# Nixie_Clock.net
KiCad netlist of a schematic drawn in Altium Designer
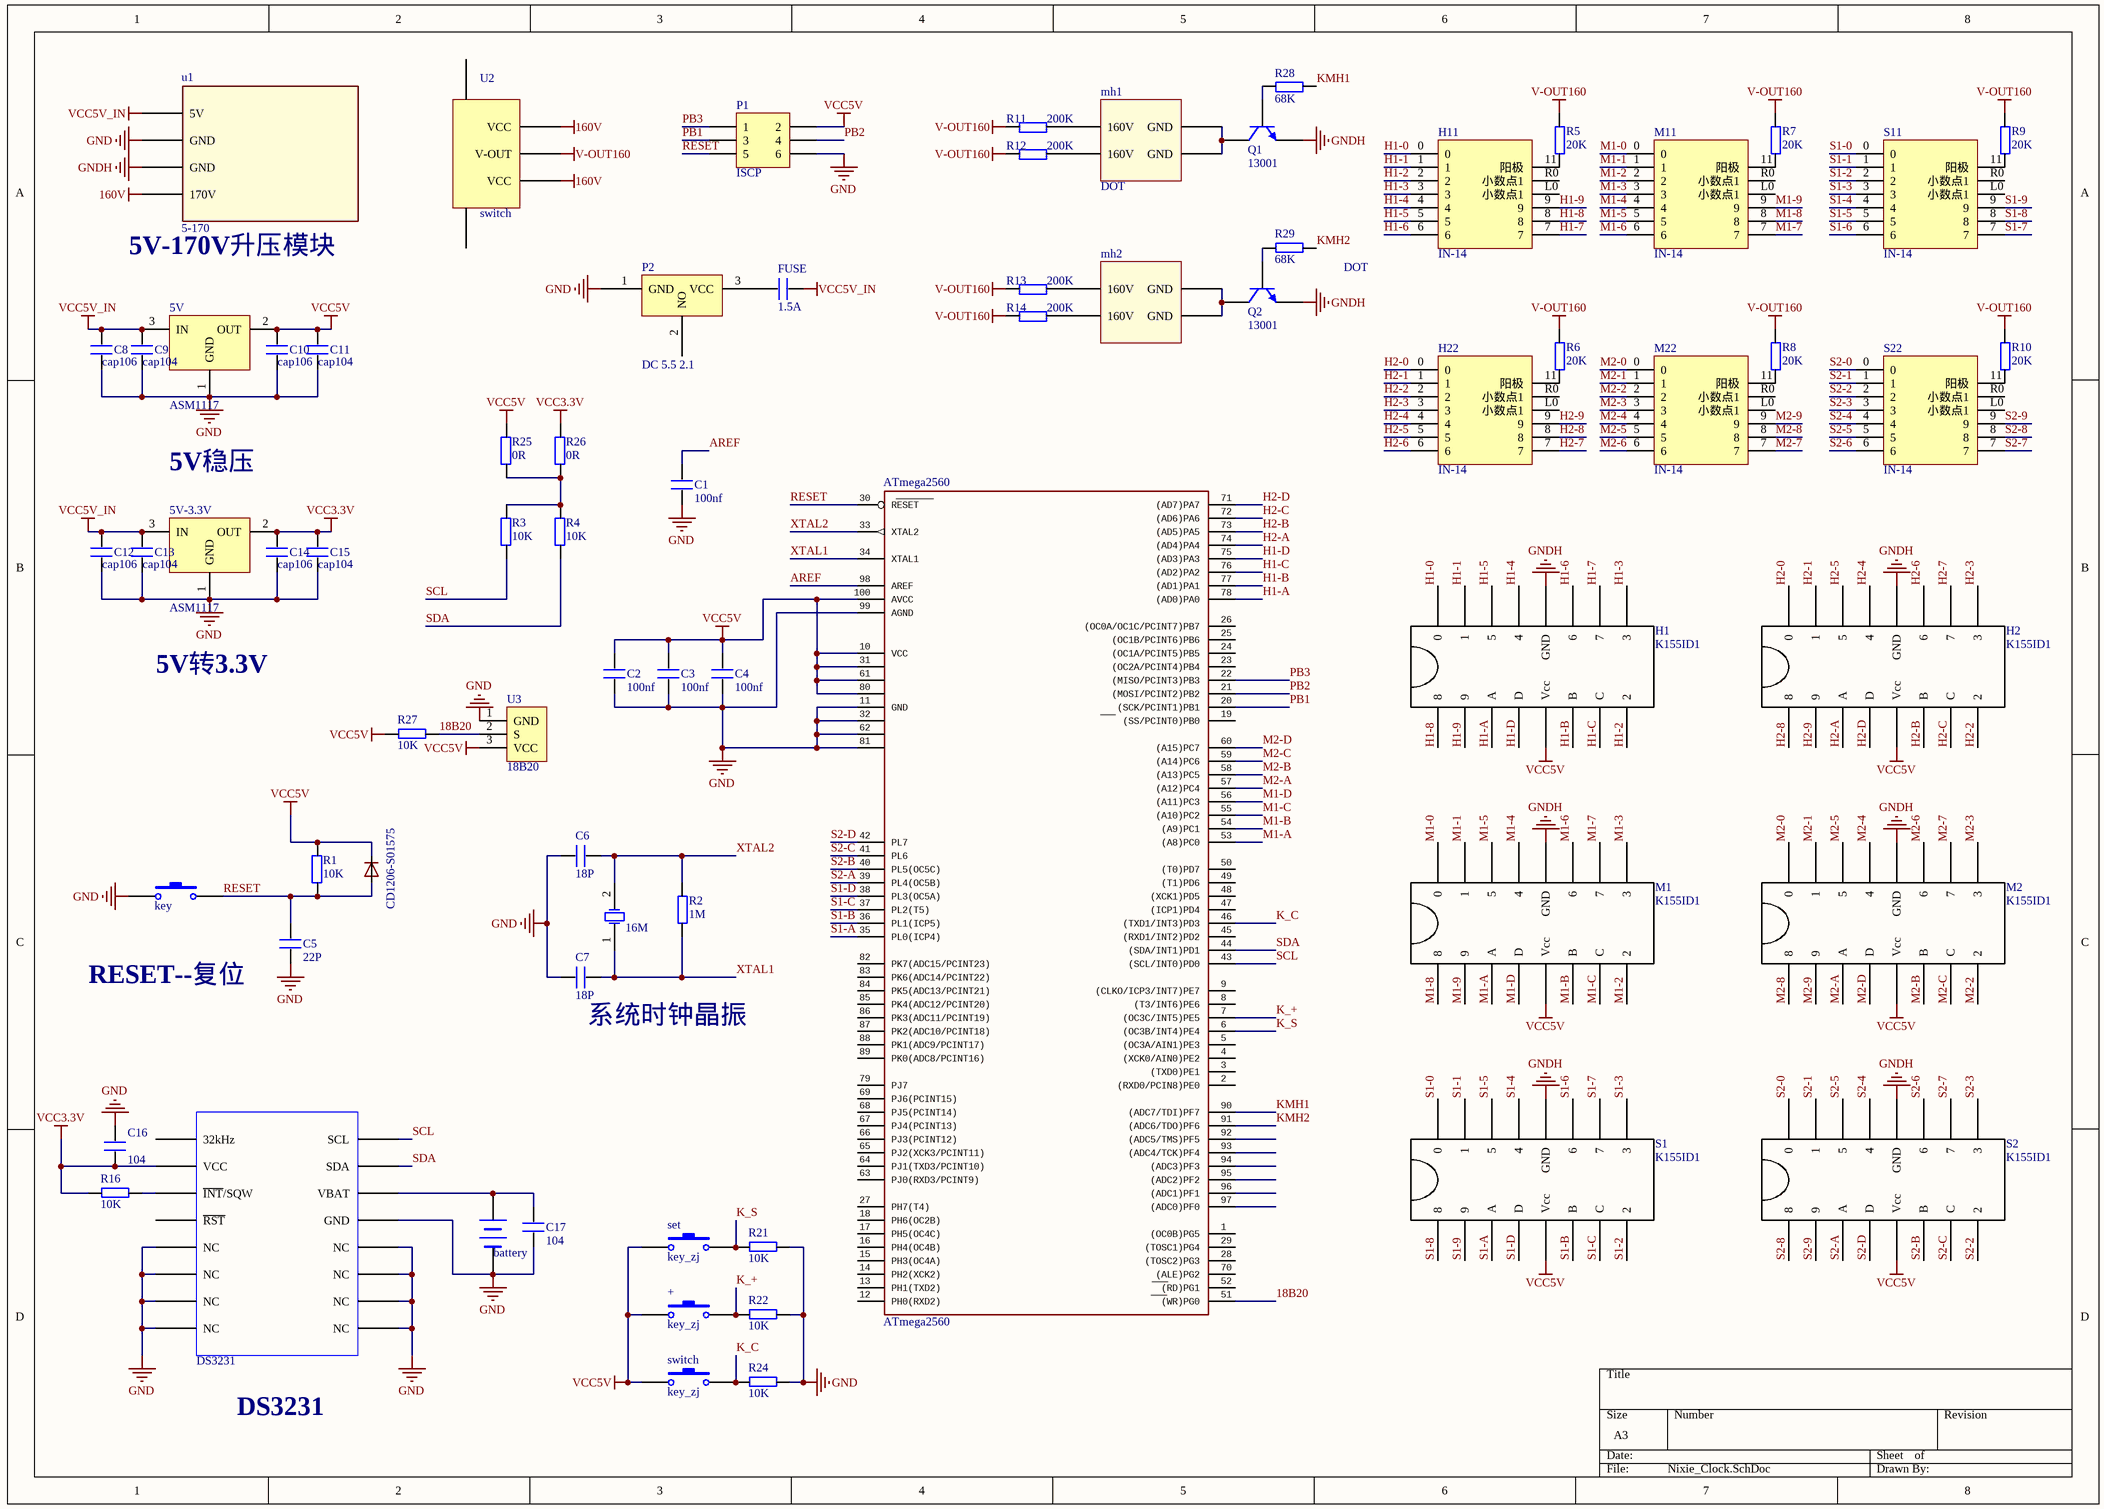
[diagram p0: Nixie_Clock.SchDoc]

(export (version "E")
  (design (tool "Eeschema 10.0.6"))
  (components
    (comp (ref "+") (value "key_zj") (footprint "key_zj") (libsource (lib "nixie") (part "key_zj")))
    (comp (ref "5V") (value "ASM1117") (footprint "AMS1117") (libsource (lib "nixie") (part "ASM1117")))
    (comp (ref "5V-3.3V") (value "ASM1117") (footprint "AMS1117") (libsource (lib "nixie") (part "ASM1117")))
    (comp (ref "ATmega2560")
      (value "ATmega2560")
      (footprint "ATmega2560")
      (libsource (lib "nixie") (part "ATmega2560"))
    )
    (comp (ref "bat") (value "battery") (footprint "battery") (libsource (lib "nixie") (part "battery")))
    (comp (ref "C1") (value "100nf") (footprint "0805_cap") (libsource (lib "nixie") (part "cap")))
    (comp (ref "C2") (value "100nf") (footprint "0805_cap") (libsource (lib "nixie") (part "cap")))
    (comp (ref "C3") (value "100nf") (footprint "0805_cap") (libsource (lib "nixie") (part "cap")))
    (comp (ref "C4") (value "100nf") (footprint "0805_cap") (libsource (lib "nixie") (part "cap")))
    (comp (ref "C5") (value "22P") (footprint "0805_cap") (libsource (lib "nixie") (part "cap")))
    (comp (ref "C6") (value "18P") (footprint "0805_cap") (libsource (lib "nixie") (part "cap")))
    (comp (ref "C7") (value "18P") (footprint "0805_cap") (libsource (lib "nixie") (part "cap")))
    (comp (ref "C8") (value "cap106") (footprint "1210_cap") (libsource (lib "nixie") (part "cap")))
    (comp (ref "C9") (value "cap104") (footprint "0805_cap") (libsource (lib "nixie") (part "cap")))
    (comp (ref "C10") (value "cap106") (footprint "1210_cap") (libsource (lib "nixie") (part "cap")))
    (comp (ref "C11") (value "cap104") (footprint "0805_cap") (libsource (lib "nixie") (part "cap")))
    (comp (ref "C12") (value "cap106") (footprint "1210_cap") (libsource (lib "nixie") (part "cap")))
    (comp (ref "C13") (value "cap104") (footprint "0805_cap") (libsource (lib "nixie") (part "cap")))
    (comp (ref "C14") (value "cap106") (footprint "1210_cap") (libsource (lib "nixie") (part "cap")))
    (comp (ref "C15") (value "cap104") (footprint "0805_cap") (libsource (lib "nixie") (part "cap")))
    (comp (ref "C16") (value "104") (footprint "0805_cap") (libsource (lib "nixie") (part "cap")))
    (comp (ref "C17") (value "104") (footprint "0805_cap") (libsource (lib "nixie") (part "cap")))
    (comp (ref "DIODE") (value "CD1206-S01575") (footprint "DIODE") (libsource (lib "nixie") (part "DIODE")))
    (comp (ref "ds3231") (value "DS3231") (footprint "DS3231") (libsource (lib "nixie") (part "DS3231")))
    (comp (ref "FUSE") (value "1.5A") (footprint "1210_cap") (libsource (lib "nixie") (part "cap")))
    (comp (ref "H1")
      (value "K155ID1")
      (footprint "Miscellaneous Devices:DIP-16")
      (libsource (lib "辉光钟第二版") (part "K155ID1"))
    )
    (comp (ref "H2")
      (value "K155ID1")
      (footprint "Miscellaneous Devices:DIP-16")
      (libsource (lib "辉光钟第二版") (part "K155ID1"))
    )
    (comp (ref "H11") (value "IN-14") (footprint "IN-14") (libsource (lib "nixie") (part "IN-14")))
    (comp (ref "H22") (value "IN-14") (footprint "IN-14") (libsource (lib "nixie") (part "IN-14")))
    (comp (ref "key") (value "key") (footprint "key") (libsource (lib "nixie") (part "key")))
    (comp (ref "M1")
      (value "K155ID1")
      (footprint "Miscellaneous Devices:DIP-16")
      (libsource (lib "辉光钟第二版") (part "K155ID1"))
    )
    (comp (ref "M2")
      (value "K155ID1")
      (footprint "Miscellaneous Devices:DIP-16")
      (libsource (lib "辉光钟第二版") (part "K155ID1"))
    )
    (comp (ref "M11") (value "IN-14") (footprint "IN-14") (libsource (lib "nixie") (part "IN-14")))
    (comp (ref "M22") (value "IN-14") (footprint "IN-14") (libsource (lib "nixie") (part "IN-14")))
    (comp (ref "mh1") (value "DOT") (footprint "dot") (libsource (lib "nixie") (part "DOT")))
    (comp (ref "mh2") (value "DOT") (footprint "dot") (libsource (lib "nixie") (part "DOT")))
    (comp (ref "P1")
      (value "ISCP")
      (footprint "HDR2X3")
      (description "Header, 3-Pin, Dual row")
      (fields (field (name "PUBLISHER") "Altium Limited"))
      (libsource (lib "Miscellaneous Connectors") (part "Header 3X2"))
    )
    (comp (ref "P2")
      (value "DC 5.5 2.1")
      (footprint "DC 5.5 2.1")
      (libsource (lib "nixie") (part "DC 5.5 2.1"))
    )
    (comp (ref "Q1") (value "13001") (footprint "13001") (libsource (lib "nixie") (part "13001")))
    (comp (ref "Q2") (value "13001") (footprint "13001") (libsource (lib "nixie") (part "13001")))
    (comp (ref "R1") (value "10K") (footprint "0805_res") (libsource (lib "nixie") (part "0805_res")))
    (comp (ref "R2") (value "1M") (footprint "0805_res") (libsource (lib "nixie") (part "0805_res")))
    (comp (ref "R3") (value "10K") (footprint "0805_res") (libsource (lib "nixie") (part "0805_res")))
    (comp (ref "R4") (value "10K") (footprint "0805_res") (libsource (lib "nixie") (part "0805_res")))
    (comp (ref "R5") (value "20K") (footprint "0805_res") (libsource (lib "nixie") (part "0805_res")))
    (comp (ref "R6") (value "20K") (footprint "0805_res") (libsource (lib "nixie") (part "0805_res")))
    (comp (ref "R7") (value "20K") (footprint "0805_res") (libsource (lib "nixie") (part "0805_res")))
    (comp (ref "R8") (value "20K") (footprint "0805_res") (libsource (lib "nixie") (part "0805_res")))
    (comp (ref "R9") (value "20K") (footprint "0805_res") (libsource (lib "nixie") (part "0805_res")))
    (comp (ref "R10") (value "20K") (footprint "0805_res") (libsource (lib "nixie") (part "0805_res")))
    (comp (ref "R11") (value "200K") (footprint "0805_res") (libsource (lib "nixie") (part "0805_res")))
    (comp (ref "R12") (value "200K") (footprint "0805_res") (libsource (lib "nixie") (part "0805_res")))
    (comp (ref "R13") (value "200K") (footprint "0805_res") (libsource (lib "nixie") (part "0805_res")))
    (comp (ref "R14") (value "200K") (footprint "0805_res") (libsource (lib "nixie") (part "0805_res")))
    (comp (ref "R16") (value "10K") (footprint "0805_res") (libsource (lib "nixie") (part "0805_res")))
    (comp (ref "R21") (value "10K") (footprint "0805_res") (libsource (lib "nixie") (part "0805_res")))
    (comp (ref "R22") (value "10K") (footprint "0805_res") (libsource (lib "nixie") (part "0805_res")))
    (comp (ref "R24") (value "10K") (footprint "0805_res") (libsource (lib "nixie") (part "0805_res")))
    (comp (ref "R25") (value "0R") (footprint "0805_res") (libsource (lib "nixie") (part "0805_res")))
    (comp (ref "R26") (value "0R") (footprint "0805_res") (libsource (lib "nixie") (part "0805_res")))
    (comp (ref "R27") (value "10K") (footprint "0805_res") (libsource (lib "nixie") (part "0805_res")))
    (comp (ref "R28") (value "68K") (footprint "0805_res") (libsource (lib "nixie") (part "0805_res")))
    (comp (ref "R29") (value "68K") (footprint "0805_res") (libsource (lib "nixie") (part "0805_res")))
    (comp (ref "S1")
      (value "K155ID1")
      (footprint "Miscellaneous Devices:DIP-16")
      (libsource (lib "辉光钟第二版") (part "K155ID1"))
    )
    (comp (ref "S2")
      (value "K155ID1")
      (footprint "Miscellaneous Devices:DIP-16")
      (libsource (lib "辉光钟第二版") (part "K155ID1"))
    )
    (comp (ref "S11") (value "IN-14") (footprint "IN-14") (libsource (lib "nixie") (part "IN-14")))
    (comp (ref "S22") (value "IN-14") (footprint "IN-14") (libsource (lib "nixie") (part "IN-14")))
    (comp (ref "set") (value "key_zj") (footprint "key_zj") (libsource (lib "nixie") (part "key_zj")))
    (comp (ref "switch") (value "key_zj") (footprint "key_zj") (libsource (lib "nixie") (part "key_zj")))
    (comp (ref "u1") (value "5-170") (footprint "5-170V") (libsource (lib "nixie") (part "5-170")))
    (comp (ref "U2") (value "switch") (footprint "switch") (libsource (lib "nixie") (part "switch")))
    (comp (ref "U3") (value "18B20") (footprint "18B20") (libsource (lib "nixie") (part "18B20")))
    (comp (ref "Y1") (value "16M") (footprint "XTAL") (libsource (lib "nixie") (part "xtal")))
  )
  (nets
    (net (code "1") (name "/18B20") (class "Default")
      (node (ref "ATmega2560") (pin "51") (pinfunction "(WR)PG0_51") (pintype "passive"))
      (node (ref "R27") (pin "1") (pintype "passive"))
      (node (ref "U3") (pin "2") (pinfunction "S_2") (pintype "passive"))
    )
    (net (code "2") (name "/AREF") (class "Default")
      (node (ref "ATmega2560") (pin "98") (pinfunction "AREF_98") (pintype "passive"))
      (node (ref "C1") (pin "2") (pintype "passive"))
    )
    (net (code "3") (name "/H1-0") (class "Default")
      (node (ref "H1") (pin "16") (pinfunction "0_16") (pintype "passive"))
      (node (ref "H11") (pin "0") (pinfunction "0_0") (pintype "passive"))
    )
    (net (code "4") (name "/H1-1") (class "Default")
      (node (ref "H1") (pin "15") (pinfunction "1_15") (pintype "passive"))
      (node (ref "H11") (pin "1") (pinfunction "1_1") (pintype "passive"))
    )
    (net (code "5") (name "/H1-2") (class "Default")
      (node (ref "H1") (pin "8") (pinfunction "2_8") (pintype "passive"))
      (node (ref "H11") (pin "2") (pinfunction "2_2") (pintype "passive"))
    )
    (net (code "6") (name "/H1-3") (class "Default")
      (node (ref "H1") (pin "9") (pinfunction "3_9") (pintype "passive"))
      (node (ref "H11") (pin "3") (pinfunction "3_3") (pintype "passive"))
    )
    (net (code "7") (name "/H1-4") (class "Default")
      (node (ref "H1") (pin "13") (pinfunction "4_13") (pintype "passive"))
      (node (ref "H11") (pin "4") (pinfunction "4_4") (pintype "passive"))
    )
    (net (code "8") (name "/H1-5") (class "Default")
      (node (ref "H1") (pin "14") (pinfunction "5_14") (pintype "passive"))
      (node (ref "H11") (pin "5") (pinfunction "5_5") (pintype "passive"))
    )
    (net (code "9") (name "/H1-6") (class "Default")
      (node (ref "H1") (pin "11") (pinfunction "6_11") (pintype "passive"))
      (node (ref "H11") (pin "6") (pinfunction "6_6") (pintype "passive"))
    )
    (net (code "10") (name "/H1-7") (class "Default")
      (node (ref "H1") (pin "10") (pinfunction "7_10") (pintype "passive"))
      (node (ref "H11") (pin "7") (pinfunction "7_7") (pintype "passive"))
    )
    (net (code "11") (name "/H1-8") (class "Default")
      (node (ref "H1") (pin "1") (pinfunction "8_1") (pintype "passive"))
      (node (ref "H11") (pin "8") (pinfunction "8_8") (pintype "passive"))
    )
    (net (code "12") (name "/H1-9") (class "Default")
      (node (ref "H1") (pin "2") (pinfunction "9_2") (pintype "passive"))
      (node (ref "H11") (pin "9") (pinfunction "9_9") (pintype "passive"))
    )
    (net (code "13") (name "/H1-A") (class "Default")
      (node (ref "ATmega2560") (pin "78") (pinfunction "(AD0)PA0_78") (pintype "passive"))
      (node (ref "H1") (pin "3") (pinfunction "A_3") (pintype "passive"))
    )
    (net (code "14") (name "/H1-B") (class "Default")
      (node (ref "ATmega2560") (pin "77") (pinfunction "(AD1)PA1_77") (pintype "passive"))
      (node (ref "H1") (pin "6") (pinfunction "B_6") (pintype "passive"))
    )
    (net (code "15") (name "/H1-C") (class "Default")
      (node (ref "ATmega2560") (pin "76") (pinfunction "(AD2)PA2_76") (pintype "passive"))
      (node (ref "H1") (pin "7") (pinfunction "C_7") (pintype "passive"))
    )
    (net (code "16") (name "/H1-D") (class "Default")
      (node (ref "ATmega2560") (pin "75") (pinfunction "(AD3)PA3_75") (pintype "passive"))
      (node (ref "H1") (pin "4") (pinfunction "D_4") (pintype "passive"))
    )
    (net (code "17") (name "/H2-0") (class "Default")
      (node (ref "H2") (pin "16") (pinfunction "0_16") (pintype "passive"))
      (node (ref "H22") (pin "0") (pinfunction "0_0") (pintype "passive"))
    )
    (net (code "18") (name "/H2-1") (class "Default")
      (node (ref "H2") (pin "15") (pinfunction "1_15") (pintype "passive"))
      (node (ref "H22") (pin "1") (pinfunction "1_1") (pintype "passive"))
    )
    (net (code "19") (name "/H2-2") (class "Default")
      (node (ref "H2") (pin "8") (pinfunction "2_8") (pintype "passive"))
      (node (ref "H22") (pin "2") (pinfunction "2_2") (pintype "passive"))
    )
    (net (code "20") (name "/H2-3") (class "Default")
      (node (ref "H2") (pin "9") (pinfunction "3_9") (pintype "passive"))
      (node (ref "H22") (pin "3") (pinfunction "3_3") (pintype "passive"))
    )
    (net (code "21") (name "/H2-4") (class "Default")
      (node (ref "H2") (pin "13") (pinfunction "4_13") (pintype "passive"))
      (node (ref "H22") (pin "4") (pinfunction "4_4") (pintype "passive"))
    )
    (net (code "22") (name "/H2-5") (class "Default")
      (node (ref "H2") (pin "14") (pinfunction "5_14") (pintype "passive"))
      (node (ref "H22") (pin "5") (pinfunction "5_5") (pintype "passive"))
    )
    (net (code "23") (name "/H2-6") (class "Default")
      (node (ref "H2") (pin "11") (pinfunction "6_11") (pintype "passive"))
      (node (ref "H22") (pin "6") (pinfunction "6_6") (pintype "passive"))
    )
    (net (code "24") (name "/H2-7") (class "Default")
      (node (ref "H2") (pin "10") (pinfunction "7_10") (pintype "passive"))
      (node (ref "H22") (pin "7") (pinfunction "7_7") (pintype "passive"))
    )
    (net (code "25") (name "/H2-8") (class "Default")
      (node (ref "H2") (pin "1") (pinfunction "8_1") (pintype "passive"))
      (node (ref "H22") (pin "8") (pinfunction "8_8") (pintype "passive"))
    )
    (net (code "26") (name "/H2-9") (class "Default")
      (node (ref "H2") (pin "2") (pinfunction "9_2") (pintype "passive"))
      (node (ref "H22") (pin "9") (pinfunction "9_9") (pintype "passive"))
    )
    (net (code "27") (name "/H2-A") (class "Default")
      (node (ref "ATmega2560") (pin "74") (pinfunction "(AD4)PA4_74") (pintype "passive"))
      (node (ref "H2") (pin "3") (pinfunction "A_3") (pintype "passive"))
    )
    (net (code "28") (name "/H2-B") (class "Default")
      (node (ref "ATmega2560") (pin "73") (pinfunction "(AD5)PA5_73") (pintype "passive"))
      (node (ref "H2") (pin "6") (pinfunction "B_6") (pintype "passive"))
    )
    (net (code "29") (name "/H2-C") (class "Default")
      (node (ref "ATmega2560") (pin "72") (pinfunction "(AD6)PA6_72") (pintype "passive"))
      (node (ref "H2") (pin "7") (pinfunction "C_7") (pintype "passive"))
    )
    (net (code "30") (name "/H2-D") (class "Default")
      (node (ref "ATmega2560") (pin "71") (pinfunction "(AD7)PA7_71") (pintype "passive"))
      (node (ref "H2") (pin "4") (pinfunction "D_4") (pintype "passive"))
    )
    (net (code "31") (name "/KMH1") (class "Default")
      (node (ref "ATmega2560") (pin "90") (pinfunction "(ADC7/TDI)PF7_90") (pintype "passive"))
      (node (ref "R28") (pin "2") (pintype "passive"))
    )
    (net (code "32") (name "/KMH2") (class "Default")
      (node (ref "ATmega2560") (pin "91") (pinfunction "(ADC6/TDO)PF6_91") (pintype "passive"))
      (node (ref "R29") (pin "1") (pintype "passive"))
    )
    (net (code "33") (name "/K_+") (class "Default")
      (node (ref "+") (pin "2") (pinfunction "2_2") (pintype "passive"))
      (node (ref "ATmega2560") (pin "7") (pinfunction "(OC3C/INT5)PE5_7") (pintype "passive"))
      (node (ref "R22") (pin "2") (pintype "passive"))
    )
    (net (code "34") (name "/K_C") (class "Default")
      (node (ref "ATmega2560") (pin "46") (pinfunction "(TXD1/INT3)PD3_46") (pintype "passive"))
      (node (ref "R24") (pin "2") (pintype "passive"))
      (node (ref "switch") (pin "2") (pinfunction "2_2") (pintype "passive"))
    )
    (net (code "35") (name "/K_S") (class "Default")
      (node (ref "ATmega2560") (pin "6") (pinfunction "(OC3B/INT4)PE4_6") (pintype "passive"))
      (node (ref "R21") (pin "2") (pintype "passive"))
      (node (ref "set") (pin "2") (pinfunction "2_2") (pintype "passive"))
    )
    (net (code "36") (name "/M1-0") (class "Default")
      (node (ref "M1") (pin "16") (pinfunction "0_16") (pintype "passive"))
      (node (ref "M11") (pin "0") (pinfunction "0_0") (pintype "passive"))
    )
    (net (code "37") (name "/M1-1") (class "Default")
      (node (ref "M1") (pin "15") (pinfunction "1_15") (pintype "passive"))
      (node (ref "M11") (pin "1") (pinfunction "1_1") (pintype "passive"))
    )
    (net (code "38") (name "/M1-2") (class "Default")
      (node (ref "M1") (pin "8") (pinfunction "2_8") (pintype "passive"))
      (node (ref "M11") (pin "2") (pinfunction "2_2") (pintype "passive"))
    )
    (net (code "39") (name "/M1-3") (class "Default")
      (node (ref "M1") (pin "9") (pinfunction "3_9") (pintype "passive"))
      (node (ref "M11") (pin "3") (pinfunction "3_3") (pintype "passive"))
    )
    (net (code "40") (name "/M1-4") (class "Default")
      (node (ref "M1") (pin "13") (pinfunction "4_13") (pintype "passive"))
      (node (ref "M11") (pin "4") (pinfunction "4_4") (pintype "passive"))
    )
    (net (code "41") (name "/M1-5") (class "Default")
      (node (ref "M1") (pin "14") (pinfunction "5_14") (pintype "passive"))
      (node (ref "M11") (pin "5") (pinfunction "5_5") (pintype "passive"))
    )
    (net (code "42") (name "/M1-6") (class "Default")
      (node (ref "M1") (pin "11") (pinfunction "6_11") (pintype "passive"))
      (node (ref "M11") (pin "6") (pinfunction "6_6") (pintype "passive"))
    )
    (net (code "43") (name "/M1-7") (class "Default")
      (node (ref "M1") (pin "10") (pinfunction "7_10") (pintype "passive"))
      (node (ref "M11") (pin "7") (pinfunction "7_7") (pintype "passive"))
    )
    (net (code "44") (name "/M1-8") (class "Default")
      (node (ref "M1") (pin "1") (pinfunction "8_1") (pintype "passive"))
      (node (ref "M11") (pin "8") (pinfunction "8_8") (pintype "passive"))
    )
    (net (code "45") (name "/M1-9") (class "Default")
      (node (ref "M1") (pin "2") (pinfunction "9_2") (pintype "passive"))
      (node (ref "M11") (pin "9") (pinfunction "9_9") (pintype "passive"))
    )
    (net (code "46") (name "/M1-A") (class "Default")
      (node (ref "ATmega2560") (pin "53") (pinfunction "(A8)PC0_53") (pintype "passive"))
      (node (ref "M1") (pin "3") (pinfunction "A_3") (pintype "passive"))
    )
    (net (code "47") (name "/M1-B") (class "Default")
      (node (ref "ATmega2560") (pin "54") (pinfunction "(A9)PC1_54") (pintype "passive"))
      (node (ref "M1") (pin "6") (pinfunction "B_6") (pintype "passive"))
    )
    (net (code "48") (name "/M1-C") (class "Default")
      (node (ref "ATmega2560") (pin "55") (pinfunction "(A10)PC2_55") (pintype "passive"))
      (node (ref "M1") (pin "7") (pinfunction "C_7") (pintype "passive"))
    )
    (net (code "49") (name "/M1-D") (class "Default")
      (node (ref "ATmega2560") (pin "56") (pinfunction "(A11)PC3_56") (pintype "passive"))
      (node (ref "M1") (pin "4") (pinfunction "D_4") (pintype "passive"))
    )
    (net (code "50") (name "/M2-0") (class "Default")
      (node (ref "M2") (pin "16") (pinfunction "0_16") (pintype "passive"))
      (node (ref "M22") (pin "0") (pinfunction "0_0") (pintype "passive"))
    )
    (net (code "51") (name "/M2-1") (class "Default")
      (node (ref "M2") (pin "15") (pinfunction "1_15") (pintype "passive"))
      (node (ref "M22") (pin "1") (pinfunction "1_1") (pintype "passive"))
    )
    (net (code "52") (name "/M2-2") (class "Default")
      (node (ref "M2") (pin "8") (pinfunction "2_8") (pintype "passive"))
      (node (ref "M22") (pin "2") (pinfunction "2_2") (pintype "passive"))
    )
    (net (code "53") (name "/M2-3") (class "Default")
      (node (ref "M2") (pin "9") (pinfunction "3_9") (pintype "passive"))
      (node (ref "M22") (pin "3") (pinfunction "3_3") (pintype "passive"))
    )
    (net (code "54") (name "/M2-4") (class "Default")
      (node (ref "M2") (pin "13") (pinfunction "4_13") (pintype "passive"))
      (node (ref "M22") (pin "4") (pinfunction "4_4") (pintype "passive"))
    )
    (net (code "55") (name "/M2-5") (class "Default")
      (node (ref "M2") (pin "14") (pinfunction "5_14") (pintype "passive"))
      (node (ref "M22") (pin "5") (pinfunction "5_5") (pintype "passive"))
    )
    (net (code "56") (name "/M2-6") (class "Default")
      (node (ref "M2") (pin "11") (pinfunction "6_11") (pintype "passive"))
      (node (ref "M22") (pin "6") (pinfunction "6_6") (pintype "passive"))
    )
    (net (code "57") (name "/M2-7") (class "Default")
      (node (ref "M2") (pin "10") (pinfunction "7_10") (pintype "passive"))
      (node (ref "M22") (pin "7") (pinfunction "7_7") (pintype "passive"))
    )
    (net (code "58") (name "/M2-8") (class "Default")
      (node (ref "M2") (pin "1") (pinfunction "8_1") (pintype "passive"))
      (node (ref "M22") (pin "8") (pinfunction "8_8") (pintype "passive"))
    )
    (net (code "59") (name "/M2-9") (class "Default")
      (node (ref "M2") (pin "2") (pinfunction "9_2") (pintype "passive"))
      (node (ref "M22") (pin "9") (pinfunction "9_9") (pintype "passive"))
    )
    (net (code "60") (name "/M2-A") (class "Default")
      (node (ref "ATmega2560") (pin "57") (pinfunction "(A12)PC4_57") (pintype "passive"))
      (node (ref "M2") (pin "3") (pinfunction "A_3") (pintype "passive"))
    )
    (net (code "61") (name "/M2-B") (class "Default")
      (node (ref "ATmega2560") (pin "58") (pinfunction "(A13)PC5_58") (pintype "passive"))
      (node (ref "M2") (pin "6") (pinfunction "B_6") (pintype "passive"))
    )
    (net (code "62") (name "/M2-C") (class "Default")
      (node (ref "ATmega2560") (pin "59") (pinfunction "(A14)PC6_59") (pintype "passive"))
      (node (ref "M2") (pin "7") (pinfunction "C_7") (pintype "passive"))
    )
    (net (code "63") (name "/M2-D") (class "Default")
      (node (ref "ATmega2560") (pin "60") (pinfunction "(A15)PC7_60") (pintype "passive"))
      (node (ref "M2") (pin "4") (pinfunction "D_4") (pintype "passive"))
    )
    (net (code "64") (name "/PB1") (class "Default")
      (node (ref "ATmega2560") (pin "20") (pinfunction "(SCK/PCINT1)PB1_20") (pintype "passive"))
      (node (ref "P1") (pin "3") (pinfunction "3_3") (pintype "passive"))
    )
    (net (code "65") (name "/PB2") (class "Default")
      (node (ref "ATmega2560") (pin "21") (pinfunction "(MOSI/PCINT2)PB2_21") (pintype "passive"))
      (node (ref "P1") (pin "4") (pinfunction "4_4") (pintype "passive"))
    )
    (net (code "66") (name "/PB3") (class "Default")
      (node (ref "ATmega2560") (pin "22") (pinfunction "(MISO/PCINT3)PB3_22") (pintype "passive"))
      (node (ref "P1") (pin "1") (pinfunction "1_1") (pintype "passive"))
    )
    (net (code "67") (name "/RESET") (class "Default")
      (node (ref "ATmega2560") (pin "30") (pinfunction "RESET_30") (pintype "passive"))
      (node (ref "C5") (pin "2") (pintype "passive"))
      (node (ref "DIODE") (pin "A") (pinfunction "A_A") (pintype "passive"))
      (node (ref "P1") (pin "5") (pinfunction "5_5") (pintype "passive"))
      (node (ref "R1") (pin "2") (pintype "passive"))
      (node (ref "key") (pin "2") (pinfunction "2_2") (pintype "passive"))
    )
    (net (code "68") (name "/S1-0") (class "Default")
      (node (ref "S1") (pin "16") (pinfunction "0_16") (pintype "passive"))
      (node (ref "S11") (pin "0") (pinfunction "0_0") (pintype "passive"))
    )
    (net (code "69") (name "/S1-1") (class "Default")
      (node (ref "S1") (pin "15") (pinfunction "1_15") (pintype "passive"))
      (node (ref "S11") (pin "1") (pinfunction "1_1") (pintype "passive"))
    )
    (net (code "70") (name "/S1-2") (class "Default")
      (node (ref "S1") (pin "8") (pinfunction "2_8") (pintype "passive"))
      (node (ref "S11") (pin "2") (pinfunction "2_2") (pintype "passive"))
    )
    (net (code "71") (name "/S1-3") (class "Default")
      (node (ref "S1") (pin "9") (pinfunction "3_9") (pintype "passive"))
      (node (ref "S11") (pin "3") (pinfunction "3_3") (pintype "passive"))
    )
    (net (code "72") (name "/S1-4") (class "Default")
      (node (ref "S1") (pin "13") (pinfunction "4_13") (pintype "passive"))
      (node (ref "S11") (pin "4") (pinfunction "4_4") (pintype "passive"))
    )
    (net (code "73") (name "/S1-5") (class "Default")
      (node (ref "S1") (pin "14") (pinfunction "5_14") (pintype "passive"))
      (node (ref "S11") (pin "5") (pinfunction "5_5") (pintype "passive"))
    )
    (net (code "74") (name "/S1-6") (class "Default")
      (node (ref "S1") (pin "11") (pinfunction "6_11") (pintype "passive"))
      (node (ref "S11") (pin "6") (pinfunction "6_6") (pintype "passive"))
    )
    (net (code "75") (name "/S1-7") (class "Default")
      (node (ref "S1") (pin "10") (pinfunction "7_10") (pintype "passive"))
      (node (ref "S11") (pin "7") (pinfunction "7_7") (pintype "passive"))
    )
    (net (code "76") (name "/S1-8") (class "Default")
      (node (ref "S1") (pin "1") (pinfunction "8_1") (pintype "passive"))
      (node (ref "S11") (pin "8") (pinfunction "8_8") (pintype "passive"))
    )
    (net (code "77") (name "/S1-9") (class "Default")
      (node (ref "S1") (pin "2") (pinfunction "9_2") (pintype "passive"))
      (node (ref "S11") (pin "9") (pinfunction "9_9") (pintype "passive"))
    )
    (net (code "78") (name "/S1-A") (class "Default")
      (node (ref "ATmega2560") (pin "35") (pinfunction "PL0(ICP4)_35") (pintype "passive"))
      (node (ref "S1") (pin "3") (pinfunction "A_3") (pintype "passive"))
    )
    (net (code "79") (name "/S1-B") (class "Default")
      (node (ref "ATmega2560") (pin "36") (pinfunction "PL1(ICP5)_36") (pintype "passive"))
      (node (ref "S1") (pin "6") (pinfunction "B_6") (pintype "passive"))
    )
    (net (code "80") (name "/S1-C") (class "Default")
      (node (ref "ATmega2560") (pin "37") (pinfunction "PL2(T5)_37") (pintype "passive"))
      (node (ref "S1") (pin "7") (pinfunction "C_7") (pintype "passive"))
    )
    (net (code "81") (name "/S1-D") (class "Default")
      (node (ref "ATmega2560") (pin "38") (pinfunction "PL3(OC5A)_38") (pintype "passive"))
      (node (ref "S1") (pin "4") (pinfunction "D_4") (pintype "passive"))
    )
    (net (code "82") (name "/S2-0") (class "Default")
      (node (ref "S2") (pin "16") (pinfunction "0_16") (pintype "passive"))
      (node (ref "S22") (pin "0") (pinfunction "0_0") (pintype "passive"))
    )
    (net (code "83") (name "/S2-1") (class "Default")
      (node (ref "S2") (pin "15") (pinfunction "1_15") (pintype "passive"))
      (node (ref "S22") (pin "1") (pinfunction "1_1") (pintype "passive"))
    )
    (net (code "84") (name "/S2-2") (class "Default")
      (node (ref "S2") (pin "8") (pinfunction "2_8") (pintype "passive"))
      (node (ref "S22") (pin "2") (pinfunction "2_2") (pintype "passive"))
    )
    (net (code "85") (name "/S2-3") (class "Default")
      (node (ref "S2") (pin "9") (pinfunction "3_9") (pintype "passive"))
      (node (ref "S22") (pin "3") (pinfunction "3_3") (pintype "passive"))
    )
    (net (code "86") (name "/S2-4") (class "Default")
      (node (ref "S2") (pin "13") (pinfunction "4_13") (pintype "passive"))
      (node (ref "S22") (pin "4") (pinfunction "4_4") (pintype "passive"))
    )
    (net (code "87") (name "/S2-5") (class "Default")
      (node (ref "S2") (pin "14") (pinfunction "5_14") (pintype "passive"))
      (node (ref "S22") (pin "5") (pinfunction "5_5") (pintype "passive"))
    )
    (net (code "88") (name "/S2-6") (class "Default")
      (node (ref "S2") (pin "11") (pinfunction "6_11") (pintype "passive"))
      (node (ref "S22") (pin "6") (pinfunction "6_6") (pintype "passive"))
    )
    (net (code "89") (name "/S2-7") (class "Default")
      (node (ref "S2") (pin "10") (pinfunction "7_10") (pintype "passive"))
      (node (ref "S22") (pin "7") (pinfunction "7_7") (pintype "passive"))
    )
    (net (code "90") (name "/S2-8") (class "Default")
      (node (ref "S2") (pin "1") (pinfunction "8_1") (pintype "passive"))
      (node (ref "S22") (pin "8") (pinfunction "8_8") (pintype "passive"))
    )
    (net (code "91") (name "/S2-9") (class "Default")
      (node (ref "S2") (pin "2") (pinfunction "9_2") (pintype "passive"))
      (node (ref "S22") (pin "9") (pinfunction "9_9") (pintype "passive"))
    )
    (net (code "92") (name "/S2-A") (class "Default")
      (node (ref "ATmega2560") (pin "39") (pinfunction "PL4(OC5B)_39") (pintype "passive"))
      (node (ref "S2") (pin "3") (pinfunction "A_3") (pintype "passive"))
    )
    (net (code "93") (name "/S2-B") (class "Default")
      (node (ref "ATmega2560") (pin "40") (pinfunction "PL5(OC5C)_40") (pintype "passive"))
      (node (ref "S2") (pin "6") (pinfunction "B_6") (pintype "passive"))
    )
    (net (code "94") (name "/S2-C") (class "Default")
      (node (ref "ATmega2560") (pin "41") (pinfunction "PL6_41") (pintype "passive"))
      (node (ref "S2") (pin "7") (pinfunction "C_7") (pintype "passive"))
    )
    (net (code "95") (name "/S2-D") (class "Default")
      (node (ref "ATmega2560") (pin "42") (pinfunction "PL7_42") (pintype "passive"))
      (node (ref "S2") (pin "4") (pinfunction "D_4") (pintype "passive"))
    )
    (net (code "96") (name "/SCL") (class "Default")
      (node (ref "ATmega2560") (pin "43") (pinfunction "(SCL/INT0)PD0_43") (pintype "passive"))
      (node (ref "R3") (pin "2") (pintype "passive"))
      (node (ref "ds3231") (pin "16") (pinfunction "SCL_16") (pintype "passive"))
    )
    (net (code "97") (name "/SDA") (class "Default")
      (node (ref "ATmega2560") (pin "44") (pinfunction "(SDA/INT1)PD1_44") (pintype "passive"))
      (node (ref "R4") (pin "2") (pintype "passive"))
      (node (ref "ds3231") (pin "15") (pinfunction "SDA_15") (pintype "passive"))
    )
    (net (code "98") (name "/XTAL1") (class "Default")
      (node (ref "ATmega2560") (pin "34") (pinfunction "XTAL1_34") (pintype "passive"))
      (node (ref "C7") (pin "1") (pintype "passive"))
      (node (ref "R2") (pin "1") (pintype "passive"))
      (node (ref "Y1") (pin "1") (pinfunction "OSC1_1") (pintype "passive"))
    )
    (net (code "99") (name "/XTAL2") (class "Default")
      (node (ref "ATmega2560") (pin "33") (pinfunction "XTAL2_33") (pintype "output"))
      (node (ref "C6") (pin "1") (pintype "passive"))
      (node (ref "R2") (pin "2") (pintype "passive"))
      (node (ref "Y1") (pin "2") (pinfunction "OSC2_2") (pintype "passive"))
    )
    (net (code "100") (name "160V") (class "Default")
      (node (ref "U2") (pin "1") (pinfunction "VCC_1") (pintype "passive"))
      (node (ref "U2") (pin "3") (pinfunction "VCC_3") (pintype "passive"))
      (node (ref "u1") (pin "4") (pinfunction "170V_4") (pintype "passive"))
    )
    (net (code "101") (name "GND") (class "Default")
      (node (ref "5V") (pin "1") (pinfunction "GND_1") (pintype "passive"))
      (node (ref "5V-3.3V") (pin "1") (pinfunction "GND_1") (pintype "passive"))
      (node (ref "ATmega2560") (pin "11") (pinfunction "GND_11") (pintype "power_in"))
      (node (ref "ATmega2560") (pin "32") (pinfunction "GND1_32") (pintype "power_in"))
      (node (ref "ATmega2560") (pin "62") (pinfunction "GND2_62") (pintype "power_in"))
      (node (ref "ATmega2560") (pin "81") (pinfunction "GND3_81") (pintype "power_in"))
      (node (ref "ATmega2560") (pin "99") (pinfunction "AGND_99") (pintype "power_in"))
      (node (ref "C1") (pin "1") (pintype "passive"))
      (node (ref "C10") (pin "1") (pintype "passive"))
      (node (ref "C11") (pin "1") (pintype "passive"))
      (node (ref "C12") (pin "1") (pintype "passive"))
      (node (ref "C13") (pin "1") (pintype "passive"))
      (node (ref "C14") (pin "1") (pintype "passive"))
      (node (ref "C15") (pin "1") (pintype "passive"))
      (node (ref "C16") (pin "2") (pintype "passive"))
      (node (ref "C17") (pin "2") (pintype "passive"))
      (node (ref "C2") (pin "1") (pintype "passive"))
      (node (ref "C3") (pin "1") (pintype "passive"))
      (node (ref "C4") (pin "1") (pintype "passive"))
      (node (ref "C5") (pin "1") (pintype "passive"))
      (node (ref "C6") (pin "2") (pintype "passive"))
      (node (ref "C7") (pin "2") (pintype "passive"))
      (node (ref "C8") (pin "1") (pintype "passive"))
      (node (ref "C9") (pin "1") (pintype "passive"))
      (node (ref "P1") (pin "6") (pinfunction "6_6") (pintype "passive"))
      (node (ref "P2") (pin "1") (pinfunction "GND_1") (pintype "passive"))
      (node (ref "R21") (pin "1") (pintype "passive"))
      (node (ref "R22") (pin "1") (pintype "passive"))
      (node (ref "R24") (pin "1") (pintype "passive"))
      (node (ref "U3") (pin "1") (pinfunction "GND_1") (pintype "passive"))
      (node (ref "bat") (pin "2") (pinfunction "-_2") (pintype "passive"))
      (node (ref "ds3231") (pin "10") (pinfunction "NC_10") (pintype "passive"))
      (node (ref "ds3231") (pin "11") (pinfunction "NC_11") (pintype "passive"))
      (node (ref "ds3231") (pin "12") (pinfunction "NC_12") (pintype "passive"))
      (node (ref "ds3231") (pin "13") (pinfunction "GND_13") (pintype "passive"))
      (node (ref "ds3231") (pin "5") (pinfunction "NC_5") (pintype "passive"))
      (node (ref "ds3231") (pin "6") (pinfunction "NC_6") (pintype "passive"))
      (node (ref "ds3231") (pin "7") (pinfunction "NC_7") (pintype "passive"))
      (node (ref "ds3231") (pin "8") (pinfunction "NC_8") (pintype "passive"))
      (node (ref "ds3231") (pin "9") (pinfunction "NC_9") (pintype "passive"))
      (node (ref "key") (pin "1") (pinfunction "1_1") (pintype "passive"))
      (node (ref "u1") (pin "2") (pinfunction "GND_2") (pintype "passive"))
    )
    (net (code "102") (name "GNDH") (class "Default")
      (node (ref "H1") (pin "12") (pinfunction "GND_12") (pintype "passive"))
      (node (ref "H2") (pin "12") (pinfunction "GND_12") (pintype "passive"))
      (node (ref "M1") (pin "12") (pinfunction "GND_12") (pintype "passive"))
      (node (ref "M2") (pin "12") (pinfunction "GND_12") (pintype "passive"))
      (node (ref "Q1") (pin "1") (pinfunction "E_1") (pintype "passive"))
      (node (ref "Q2") (pin "1") (pinfunction "E_1") (pintype "passive"))
      (node (ref "S1") (pin "12") (pinfunction "GND_12") (pintype "passive"))
      (node (ref "S2") (pin "12") (pinfunction "GND_12") (pintype "passive"))
      (node (ref "u1") (pin "3") (pinfunction "GND_3") (pintype "passive"))
    )
    (net (code "103") (name "Net-(H11-阳极)") (class "Default")
      (node (ref "H11") (pin "11") (pinfunction "阳极_11") (pintype "passive"))
      (node (ref "R5") (pin "1") (pintype "passive"))
    )
    (net (code "104") (name "Net-(H22-阳极)") (class "Default")
      (node (ref "H22") (pin "11") (pinfunction "阳极_11") (pintype "passive"))
      (node (ref "R6") (pin "1") (pintype "passive"))
    )
    (net (code "105") (name "Net-(M11-阳极)") (class "Default")
      (node (ref "M11") (pin "11") (pinfunction "阳极_11") (pintype "passive"))
      (node (ref "R7") (pin "1") (pintype "passive"))
    )
    (net (code "106") (name "Net-(M22-阳极)") (class "Default")
      (node (ref "M22") (pin "11") (pinfunction "阳极_11") (pintype "passive"))
      (node (ref "R8") (pin "1") (pintype "passive"))
    )
    (net (code "107") (name "Net-(P2-VCC)") (class "Default")
      (node (ref "FUSE") (pin "1") (pintype "passive"))
      (node (ref "P2") (pin "3") (pinfunction "VCC_3") (pintype "passive"))
    )
    (net (code "108") (name "Net-(Q1-B)") (class "Default")
      (node (ref "Q1") (pin "3") (pinfunction "B_3") (pintype "passive"))
      (node (ref "R28") (pin "1") (pintype "passive"))
    )
    (net (code "109") (name "Net-(Q1-C)") (class "Default")
      (node (ref "Q1") (pin "2") (pinfunction "C_2") (pintype "passive"))
      (node (ref "mh1") (pin "2") (pinfunction "GND_2") (pintype "passive"))
      (node (ref "mh1") (pin "4") (pinfunction "GND_4") (pintype "passive"))
    )
    (net (code "110") (name "Net-(Q2-B)") (class "Default")
      (node (ref "Q2") (pin "3") (pinfunction "B_3") (pintype "passive"))
      (node (ref "R29") (pin "2") (pintype "passive"))
    )
    (net (code "111") (name "Net-(Q2-C)") (class "Default")
      (node (ref "Q2") (pin "2") (pinfunction "C_2") (pintype "passive"))
      (node (ref "mh2") (pin "2") (pinfunction "GND_2") (pintype "passive"))
      (node (ref "mh2") (pin "4") (pinfunction "GND_4") (pintype "passive"))
    )
    (net (code "112") (name "Net-(R11-Pad2)") (class "Default")
      (node (ref "R11") (pin "2") (pintype "passive"))
      (node (ref "mh1") (pin "1") (pinfunction "160V_1") (pintype "passive"))
    )
    (net (code "113") (name "Net-(R12-Pad2)") (class "Default")
      (node (ref "R12") (pin "2") (pintype "passive"))
      (node (ref "mh1") (pin "3") (pinfunction "160V_3") (pintype "passive"))
    )
    (net (code "114") (name "Net-(R13-Pad2)") (class "Default")
      (node (ref "R13") (pin "2") (pintype "passive"))
      (node (ref "mh2") (pin "1") (pinfunction "160V_1") (pintype "passive"))
    )
    (net (code "115") (name "Net-(R14-Pad2)") (class "Default")
      (node (ref "R14") (pin "2") (pintype "passive"))
      (node (ref "mh2") (pin "3") (pinfunction "160V_3") (pintype "passive"))
    )
    (net (code "116") (name "Net-(R25-Pad2)") (class "Default")
      (node (ref "R25") (pin "2") (pintype "passive"))
      (node (ref "R26") (pin "2") (pintype "passive"))
      (node (ref "R3") (pin "1") (pintype "passive"))
      (node (ref "R4") (pin "1") (pintype "passive"))
    )
    (net (code "117") (name "Net-(S11-阳极)") (class "Default")
      (node (ref "R9") (pin "1") (pintype "passive"))
      (node (ref "S11") (pin "11") (pinfunction "阳极_11") (pintype "passive"))
    )
    (net (code "118") (name "Net-(S22-阳极)") (class "Default")
      (node (ref "R10") (pin "1") (pintype "passive"))
      (node (ref "S22") (pin "11") (pinfunction "阳极_11") (pintype "passive"))
    )
    (net (code "119") (name "Net-(bat-+)") (class "Default")
      (node (ref "C17") (pin "1") (pintype "passive"))
      (node (ref "bat") (pin "1") (pinfunction "+_1") (pintype "passive"))
      (node (ref "ds3231") (pin "14") (pinfunction "VBAT_14") (pintype "passive"))
    )
    (net (code "120") (name "Net-(ds3231-~{INT}{slash}SQW)") (class "Default")
      (node (ref "R16") (pin "1") (pintype "passive"))
      (node (ref "ds3231") (pin "3") (pinfunction "~{INT}/SQW_3") (pintype "passive"))
    )
    (net (code "121") (name "V-OUT160") (class "Default")
      (node (ref "R10") (pin "2") (pintype "passive"))
      (node (ref "R11") (pin "1") (pintype "passive"))
      (node (ref "R12") (pin "1") (pintype "passive"))
      (node (ref "R13") (pin "1") (pintype "passive"))
      (node (ref "R14") (pin "1") (pintype "passive"))
      (node (ref "R5") (pin "2") (pintype "passive"))
      (node (ref "R6") (pin "2") (pintype "passive"))
      (node (ref "R7") (pin "2") (pintype "passive"))
      (node (ref "R8") (pin "2") (pintype "passive"))
      (node (ref "R9") (pin "2") (pintype "passive"))
      (node (ref "U2") (pin "2") (pinfunction "V-OUT_2") (pintype "passive"))
    )
    (net (code "122") (name "VCC3.3V") (class "Default")
      (node (ref "5V-3.3V") (pin "2") (pinfunction "OUT_2") (pintype "passive"))
      (node (ref "C14") (pin "2") (pintype "passive"))
      (node (ref "C15") (pin "2") (pintype "passive"))
      (node (ref "C16") (pin "1") (pintype "passive"))
      (node (ref "R16") (pin "2") (pintype "passive"))
      (node (ref "R26") (pin "1") (pintype "passive"))
      (node (ref "ds3231") (pin "2") (pinfunction "VCC_2") (pintype "passive"))
    )
    (net (code "123") (name "VCC5V") (class "Default")
      (node (ref "+") (pin "1") (pinfunction "1_1") (pintype "passive"))
      (node (ref "5V") (pin "2") (pinfunction "OUT_2") (pintype "passive"))
      (node (ref "ATmega2560") (pin "10") (pinfunction "VCC_10") (pintype "power_in"))
      (node (ref "ATmega2560") (pin "100") (pinfunction "AVCC_100") (pintype "power_in"))
      (node (ref "ATmega2560") (pin "31") (pinfunction "VCC1_31") (pintype "power_in"))
      (node (ref "ATmega2560") (pin "61") (pinfunction "VCC2_61") (pintype "power_in"))
      (node (ref "ATmega2560") (pin "80") (pinfunction "VCC3_80") (pintype "power_in"))
      (node (ref "C10") (pin "2") (pintype "passive"))
      (node (ref "C11") (pin "2") (pintype "passive"))
      (node (ref "C2") (pin "2") (pintype "passive"))
      (node (ref "C3") (pin "2") (pintype "passive"))
      (node (ref "C4") (pin "2") (pintype "passive"))
      (node (ref "DIODE") (pin "C") (pinfunction "C_C") (pintype "passive"))
      (node (ref "H1") (pin "5") (pinfunction "Vcc_5") (pintype "passive"))
      (node (ref "H2") (pin "5") (pinfunction "Vcc_5") (pintype "passive"))
      (node (ref "M1") (pin "5") (pinfunction "Vcc_5") (pintype "passive"))
      (node (ref "M2") (pin "5") (pinfunction "Vcc_5") (pintype "passive"))
      (node (ref "P1") (pin "2") (pinfunction "2_2") (pintype "passive"))
      (node (ref "R1") (pin "1") (pintype "passive"))
      (node (ref "R25") (pin "1") (pintype "passive"))
      (node (ref "R27") (pin "2") (pintype "passive"))
      (node (ref "S1") (pin "5") (pinfunction "Vcc_5") (pintype "passive"))
      (node (ref "S2") (pin "5") (pinfunction "Vcc_5") (pintype "passive"))
      (node (ref "U3") (pin "3") (pinfunction "VCC_3") (pintype "passive"))
      (node (ref "set") (pin "1") (pinfunction "1_1") (pintype "passive"))
      (node (ref "switch") (pin "1") (pinfunction "1_1") (pintype "passive"))
    )
    (net (code "124") (name "VCC5V_IN") (class "Default")
      (node (ref "5V") (pin "3") (pinfunction "IN_3") (pintype "passive"))
      (node (ref "5V-3.3V") (pin "3") (pinfunction "IN_3") (pintype "passive"))
      (node (ref "C12") (pin "2") (pintype "passive"))
      (node (ref "C13") (pin "2") (pintype "passive"))
      (node (ref "C8") (pin "2") (pintype "passive"))
      (node (ref "C9") (pin "2") (pintype "passive"))
      (node (ref "FUSE") (pin "2") (pintype "passive"))
      (node (ref "u1") (pin "1") (pinfunction "5V_1") (pintype "passive"))
    )
    (net (code "125") (name "unconnected-(ATmega2560-(ADC0)PF0-Pad97)") (class "Default")
      (node (ref "ATmega2560") (pin "97") (pinfunction "(ADC0)PF0_97") (pintype "passive"))
    )
    (net (code "126") (name "unconnected-(ATmega2560-(ADC1)PF1-Pad96)") (class "Default")
      (node (ref "ATmega2560") (pin "96") (pinfunction "(ADC1)PF1_96") (pintype "passive"))
    )
    (net (code "127") (name "unconnected-(ATmega2560-(ADC2)PF2-Pad95)") (class "Default")
      (node (ref "ATmega2560") (pin "95") (pinfunction "(ADC2)PF2_95") (pintype "passive"))
    )
    (net (code "128") (name "unconnected-(ATmega2560-(ADC3)PF3-Pad94)") (class "Default")
      (node (ref "ATmega2560") (pin "94") (pinfunction "(ADC3)PF3_94") (pintype "passive"))
    )
    (net (code "129") (name "unconnected-(ATmega2560-(ADC4{slash}TCK)PF4-Pad93)") (class "Default")
      (node (ref "ATmega2560") (pin "93") (pinfunction "(ADC4/TCK)PF4_93") (pintype "passive"))
    )
    (net (code "130") (name "unconnected-(ATmega2560-(ADC5{slash}TMS)PF5-Pad92)") (class "Default")
      (node (ref "ATmega2560") (pin "92") (pinfunction "(ADC5/TMS)PF5_92") (pintype "passive"))
    )
    (net (code "131") (name "unconnected-(ATmega2560-(ALE)PG2-Pad70)") (class "Default")
      (node (ref "ATmega2560") (pin "70") (pinfunction "(ALE)PG2_70") (pintype "passive"))
    )
    (net (code "132") (name "unconnected-(ATmega2560-(CLKO{slash}ICP3{slash}INT7)PE7-Pad9)") (class "Default")
      (node (ref "ATmega2560") (pin "9") (pinfunction "(CLKO/ICP3/INT7)PE7_9") (pintype "passive"))
    )
    (net (code "133") (name "unconnected-(ATmega2560-(ICP1)PD4-Pad47)") (class "Default")
      (node (ref "ATmega2560") (pin "47") (pinfunction "(ICP1)PD4_47") (pintype "passive"))
    )
    (net (code "134") (name "unconnected-(ATmega2560-(OC0A{slash}OC1C{slash}PCINT7)PB7-Pad26)") (class "Default")
      (node (ref "ATmega2560") (pin "26") (pinfunction "(OC0A/OC1C/PCINT7)PB7_26") (pintype "passive"))
    )
    (net (code "135") (name "unconnected-(ATmega2560-(OC0B)PG5-Pad1)") (class "Default")
      (node (ref "ATmega2560") (pin "1") (pinfunction "(OC0B)PG5_1") (pintype "passive"))
    )
    (net (code "136") (name "unconnected-(ATmega2560-(OC1A{slash}PCINT5)PB5-Pad24)") (class "Default")
      (node (ref "ATmega2560") (pin "24") (pinfunction "(OC1A/PCINT5)PB5_24") (pintype "passive"))
    )
    (net (code "137") (name "unconnected-(ATmega2560-(OC1B{slash}PCINT6)PB6-Pad25)") (class "Default")
      (node (ref "ATmega2560") (pin "25") (pinfunction "(OC1B/PCINT6)PB6_25") (pintype "passive"))
    )
    (net (code "138") (name "unconnected-(ATmega2560-(OC2A{slash}PCINT4)PB4-Pad23)") (class "Default")
      (node (ref "ATmega2560") (pin "23") (pinfunction "(OC2A/PCINT4)PB4_23") (pintype "passive"))
    )
    (net (code "139") (name "unconnected-(ATmega2560-(OC3A{slash}AIN1)PE3-Pad5)") (class "Default")
      (node (ref "ATmega2560") (pin "5") (pinfunction "(OC3A/AIN1)PE3_5") (pintype "passive"))
    )
    (net (code "140") (name "unconnected-(ATmega2560-(RD)PG1-Pad52)") (class "Default")
      (node (ref "ATmega2560") (pin "52") (pinfunction "(RD)PG1_52") (pintype "passive"))
    )
    (net (code "141") (name "unconnected-(ATmega2560-(RXD0{slash}PCIN8)PE0-Pad2)") (class "Default")
      (node (ref "ATmega2560") (pin "2") (pinfunction "(RXD0/PCIN8)PE0_2") (pintype "passive"))
    )
    (net (code "142") (name "unconnected-(ATmega2560-(RXD1{slash}INT2)PD2-Pad45)") (class "Default")
      (node (ref "ATmega2560") (pin "45") (pinfunction "(RXD1/INT2)PD2_45") (pintype "passive"))
    )
    (net (code "143") (name "unconnected-(ATmega2560-(SS{slash}PCINT0)PB0-Pad19)") (class "Default")
      (node (ref "ATmega2560") (pin "19") (pinfunction "(SS/PCINT0)PB0_19") (pintype "passive"))
    )
    (net (code "144") (name "unconnected-(ATmega2560-(T0)PD7-Pad50)") (class "Default")
      (node (ref "ATmega2560") (pin "50") (pinfunction "(T0)PD7_50") (pintype "passive"))
    )
    (net (code "145") (name "unconnected-(ATmega2560-(T1)PD6-Pad49)") (class "Default")
      (node (ref "ATmega2560") (pin "49") (pinfunction "(T1)PD6_49") (pintype "passive"))
    )
    (net (code "146") (name "unconnected-(ATmega2560-(T3{slash}INT6)PE6-Pad8)") (class "Default")
      (node (ref "ATmega2560") (pin "8") (pinfunction "(T3/INT6)PE6_8") (pintype "passive"))
    )
    (net (code "147") (name "unconnected-(ATmega2560-(TOSC1)PG4-Pad29)") (class "Default")
      (node (ref "ATmega2560") (pin "29") (pinfunction "(TOSC1)PG4_29") (pintype "passive"))
    )
    (net (code "148") (name "unconnected-(ATmega2560-(TOSC2)PG3-Pad28)") (class "Default")
      (node (ref "ATmega2560") (pin "28") (pinfunction "(TOSC2)PG3_28") (pintype "passive"))
    )
    (net (code "149") (name "unconnected-(ATmega2560-(TXD0)PE1-Pad3)") (class "Default")
      (node (ref "ATmega2560") (pin "3") (pinfunction "(TXD0)PE1_3") (pintype "passive"))
    )
    (net (code "150") (name "unconnected-(ATmega2560-(XCK0{slash}AIN0)PE2-Pad4)") (class "Default")
      (node (ref "ATmega2560") (pin "4") (pinfunction "(XCK0/AIN0)PE2_4") (pintype "passive"))
    )
    (net (code "151") (name "unconnected-(ATmega2560-(XCK1)PD5-Pad48)") (class "Default")
      (node (ref "ATmega2560") (pin "48") (pinfunction "(XCK1)PD5_48") (pintype "passive"))
    )
    (net (code "152") (name "unconnected-(ATmega2560-PH0(RXD2)-Pad12)") (class "Default")
      (node (ref "ATmega2560") (pin "12") (pinfunction "PH0(RXD2)_12") (pintype "passive"))
    )
    (net (code "153") (name "unconnected-(ATmega2560-PH1(TXD2)-Pad13)") (class "Default")
      (node (ref "ATmega2560") (pin "13") (pinfunction "PH1(TXD2)_13") (pintype "passive"))
    )
    (net (code "154") (name "unconnected-(ATmega2560-PH2(XCK2)-Pad14)") (class "Default")
      (node (ref "ATmega2560") (pin "14") (pinfunction "PH2(XCK2)_14") (pintype "passive"))
    )
    (net (code "155") (name "unconnected-(ATmega2560-PH3(OC4A)-Pad15)") (class "Default")
      (node (ref "ATmega2560") (pin "15") (pinfunction "PH3(OC4A)_15") (pintype "passive"))
    )
    (net (code "156") (name "unconnected-(ATmega2560-PH4(OC4B)-Pad16)") (class "Default")
      (node (ref "ATmega2560") (pin "16") (pinfunction "PH4(OC4B)_16") (pintype "passive"))
    )
    (net (code "157") (name "unconnected-(ATmega2560-PH5(OC4C)-Pad17)") (class "Default")
      (node (ref "ATmega2560") (pin "17") (pinfunction "PH5(OC4C)_17") (pintype "passive"))
    )
    (net (code "158") (name "unconnected-(ATmega2560-PH6(OC2B)-Pad18)") (class "Default")
      (node (ref "ATmega2560") (pin "18") (pinfunction "PH6(OC2B)_18") (pintype "passive"))
    )
    (net (code "159") (name "unconnected-(ATmega2560-PH7(T4)-Pad27)") (class "Default")
      (node (ref "ATmega2560") (pin "27") (pinfunction "PH7(T4)_27") (pintype "passive"))
    )
    (net (code "160") (name "unconnected-(ATmega2560-PJ0(RXD3{slash}PCINT9)-Pad63)") (class "Default")
      (node (ref "ATmega2560") (pin "63") (pinfunction "PJ0(RXD3/PCINT9)_63") (pintype "passive"))
    )
    (net (code "161") (name "unconnected-(ATmega2560-PJ1(TXD3{slash}PCINT10)-Pad64)") (class "Default")
      (node (ref "ATmega2560") (pin "64") (pinfunction "PJ1(TXD3/PCINT10)_64") (pintype "passive"))
    )
    (net (code "162") (name "unconnected-(ATmega2560-PJ2(XCK3{slash}PCINT11)-Pad65)") (class "Default")
      (node (ref "ATmega2560") (pin "65") (pinfunction "PJ2(XCK3/PCINT11)_65") (pintype "passive"))
    )
    (net (code "163") (name "unconnected-(ATmega2560-PJ3(PCINT12)-Pad66)") (class "Default")
      (node (ref "ATmega2560") (pin "66") (pinfunction "PJ3(PCINT12)_66") (pintype "passive"))
    )
    (net (code "164") (name "unconnected-(ATmega2560-PJ4(PCINT13)-Pad67)") (class "Default")
      (node (ref "ATmega2560") (pin "67") (pinfunction "PJ4(PCINT13)_67") (pintype "passive"))
    )
    (net (code "165") (name "unconnected-(ATmega2560-PJ5(PCINT14)-Pad68)") (class "Default")
      (node (ref "ATmega2560") (pin "68") (pinfunction "PJ5(PCINT14)_68") (pintype "passive"))
    )
    (net (code "166") (name "unconnected-(ATmega2560-PJ6(PCINT15)-Pad69)") (class "Default")
      (node (ref "ATmega2560") (pin "69") (pinfunction "PJ6(PCINT15)_69") (pintype "passive"))
    )
    (net (code "167") (name "unconnected-(ATmega2560-PJ7-Pad79)") (class "Default")
      (node (ref "ATmega2560") (pin "79") (pinfunction "PJ7_79") (pintype "passive"))
    )
    (net (code "168") (name "unconnected-(ATmega2560-PK0(ADC8{slash}PCINT16)-Pad89)") (class "Default")
      (node (ref "ATmega2560") (pin "89") (pinfunction "PK0(ADC8/PCINT16)_89") (pintype "passive"))
    )
    (net (code "169") (name "unconnected-(ATmega2560-PK1(ADC9{slash}PCINT17)-Pad88)") (class "Default")
      (node (ref "ATmega2560") (pin "88") (pinfunction "PK1(ADC9/PCINT17)_88") (pintype "passive"))
    )
    (net (code "170") (name "unconnected-(ATmega2560-PK2(ADC10{slash}PCINT18)-Pad87)") (class "Default")
      (node (ref "ATmega2560") (pin "87") (pinfunction "PK2(ADC10/PCINT18)_87") (pintype "passive"))
    )
    (net (code "171") (name "unconnected-(ATmega2560-PK3(ADC11{slash}PCINT19)-Pad86)") (class "Default")
      (node (ref "ATmega2560") (pin "86") (pinfunction "PK3(ADC11/PCINT19)_86") (pintype "passive"))
    )
    (net (code "172") (name "unconnected-(ATmega2560-PK4(ADC12{slash}PCINT20)-Pad85)") (class "Default")
      (node (ref "ATmega2560") (pin "85") (pinfunction "PK4(ADC12/PCINT20)_85") (pintype "passive"))
    )
    (net (code "173") (name "unconnected-(ATmega2560-PK5(ADC13{slash}PCINT21)-Pad84)") (class "Default")
      (node (ref "ATmega2560") (pin "84") (pinfunction "PK5(ADC13/PCINT21)_84") (pintype "passive"))
    )
    (net (code "174") (name "unconnected-(ATmega2560-PK6(ADC14{slash}PCINT22)-Pad83)") (class "Default")
      (node (ref "ATmega2560") (pin "83") (pinfunction "PK6(ADC14/PCINT22)_83") (pintype "passive"))
    )
    (net (code "175") (name "unconnected-(ATmega2560-PK7(ADC15{slash}PCINT23)-Pad82)") (class "Default")
      (node (ref "ATmega2560") (pin "82") (pinfunction "PK7(ADC15/PCINT23)_82") (pintype "passive"))
    )
    (net (code "176") (name "unconnected-(H11-小数点1-PadL0)") (class "Default")
      (node (ref "H11") (pin "L0") (pinfunction "小数点1_L0") (pintype "passive"))
    )
    (net (code "177") (name "unconnected-(H11-小数点1-PadR0)") (class "Default")
      (node (ref "H11") (pin "R0") (pinfunction "小数点1_R0") (pintype "passive"))
    )
    (net (code "178") (name "unconnected-(H22-小数点1-PadL0)") (class "Default")
      (node (ref "H22") (pin "L0") (pinfunction "小数点1_L0") (pintype "passive"))
    )
    (net (code "179") (name "unconnected-(H22-小数点1-PadR0)") (class "Default")
      (node (ref "H22") (pin "R0") (pinfunction "小数点1_R0") (pintype "passive"))
    )
    (net (code "180") (name "unconnected-(M11-小数点1-PadL0)") (class "Default")
      (node (ref "M11") (pin "L0") (pinfunction "小数点1_L0") (pintype "passive"))
    )
    (net (code "181") (name "unconnected-(M11-小数点1-PadR0)") (class "Default")
      (node (ref "M11") (pin "R0") (pinfunction "小数点1_R0") (pintype "passive"))
    )
    (net (code "182") (name "unconnected-(M22-小数点1-PadL0)") (class "Default")
      (node (ref "M22") (pin "L0") (pinfunction "小数点1_L0") (pintype "passive"))
    )
    (net (code "183") (name "unconnected-(M22-小数点1-PadR0)") (class "Default")
      (node (ref "M22") (pin "R0") (pinfunction "小数点1_R0") (pintype "passive"))
    )
    (net (code "184") (name "unconnected-(P2-NO-Pad2)") (class "Default")
      (node (ref "P2") (pin "2") (pinfunction "NO_2") (pintype "passive"))
    )
    (net (code "185") (name "unconnected-(S11-小数点1-PadL0)") (class "Default")
      (node (ref "S11") (pin "L0") (pinfunction "小数点1_L0") (pintype "passive"))
    )
    (net (code "186") (name "unconnected-(S11-小数点1-PadR0)") (class "Default")
      (node (ref "S11") (pin "R0") (pinfunction "小数点1_R0") (pintype "passive"))
    )
    (net (code "187") (name "unconnected-(S22-小数点1-PadL0)") (class "Default")
      (node (ref "S22") (pin "L0") (pinfunction "小数点1_L0") (pintype "passive"))
    )
    (net (code "188") (name "unconnected-(S22-小数点1-PadR0)") (class "Default")
      (node (ref "S22") (pin "R0") (pinfunction "小数点1_R0") (pintype "passive"))
    )
    (net (code "189") (name "unconnected-(U2-Pad4)") (class "Default")
      (node (ref "U2") (pin "4") (pinfunction "4_4") (pintype "passive"))
    )
    (net (code "190") (name "unconnected-(U2-Pad5)") (class "Default")
      (node (ref "U2") (pin "5") (pinfunction "5_5") (pintype "passive"))
    )
    (net (code "191") (name "unconnected-(ds3231-32kHz-Pad1)") (class "Default")
      (node (ref "ds3231") (pin "1") (pinfunction "32kHz_1") (pintype "passive"))
    )
    (net (code "192") (name "unconnected-(ds3231-~{RST}-Pad4)") (class "Default")
      (node (ref "ds3231") (pin "4") (pinfunction "~{RST}_4") (pintype "passive"))
    )
  )
)
